# MP1584_rule.net
KiCad netlist of a schematic drawn in Altium Designer
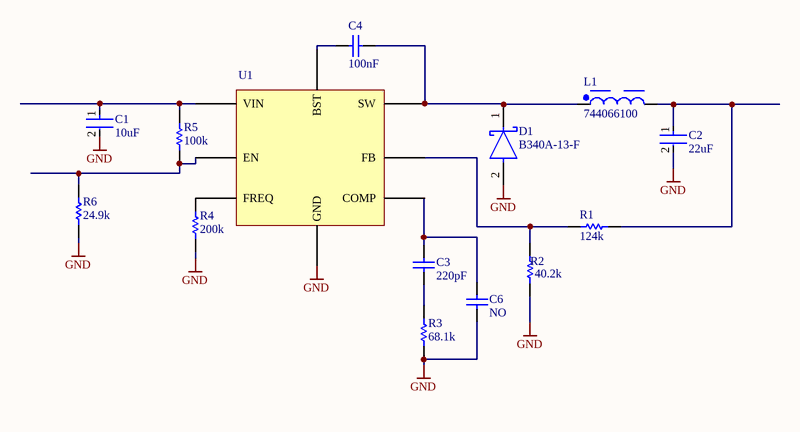
[diagram p0: MP1584_rule.SchDoc]

(export (version "E")
  (design (tool "Eeschema 10.0.6"))
  (components
    (comp (ref "C1")
      (value "10uF")
      (footprint "FP-C5750-230-0_4-MFG")
      (description "Multilayer Ceramic Capacitors 10uF ±10% 50V X5R SMD 2220")
      (fields (field (name "TOLERANCE") "10%") (field (name "VOLTAGE") "50V"))
      (libsource (lib "Altium Content Vault") (part "02cd4be3c70576c341d710602a673aa"))
    )
    (comp (ref "C2")
      (value "22uF")
      (footprint "FP-C5750-230-0_4-MFG")
      (description "Multilayer Ceramic Capacitors 10uF ±10% 50V X5R SMD 2220")
      (fields (field (name "TOLERANCE") "10%") (field (name "VOLTAGE") "50V"))
      (libsource (lib "Altium Content Vault") (part "02cd4be3c70576c341d710602a673aa"))
    )
    (comp (ref "C3")
      (value "220pF")
      (footprint "CAPC2013X88X50LL20T25")
      (fields (field (name "PART NUMBER") "C0805X221J1GACTU") (field (name "MANUFACTURER") "Kemet"))
      (libsource (lib "Altium Content Vault") (part "CAP"))
    )
    (comp (ref "C4")
      (value "100nF")
      (footprint "CAPC2013X145X48NL20T23")
      (fields (field (name "MANUFACTURER") "Vitramon") (field (name "PART NUMBER") "VJ0805Y104KXXAT"))
      (libsource (lib "Altium Content Vault") (part "CAP"))
    )
    (comp (ref "C6")
      (value "NO")
      (footprint "CAPC2013X88X50LL20T25")
      (fields (field (name "PART NUMBER") "C0805X221J1GACTU") (field (name "MANUFACTURER") "Kemet"))
      (libsource (lib "Altium Content Vault") (part "CAP"))
    )
    (comp (ref "D1")
      (value "B340A-13-F")
      (footprint "FP-SMA-MFG")
      (description "DIODE SCHOTTKY 40V 3A SMA")
      (fields (field (name "VOLTAGE") "40V"))
      (libsource (lib "Altium Content Vault") (part "1d6ec82d83fb6aee721767c19dac4b9"))
    )
    (comp (ref "L1")
      (value "744066100")
      (footprint "WE-TPC_1038")
      (fields (field (name "TOLERANCE") "30%"))
      (libsource (lib "Altium Content Vault") (part "Inductor - 2"))
    )
    (comp (ref "R1")
      (value "124k")
      (footprint "RESC2013X70X40LL20T20")
      (fields (field (name "MANUFACTURER") "Panasonic") (field (name "PART NUMBER") "ERJ-6GEYJ121V"))
      (libsource (lib "Altium Content Vault") (part "RES"))
    )
    (comp (ref "R2")
      (value "40.2k")
      (footprint "RESC2013X70X40ML20T20")
      (fields (field (name "MANUFACTURER") "Panasonic") (field (name "PART NUMBER") "ERJ6ENF4702V"))
      (libsource (lib "Altium Content Vault") (part "RES"))
    )
    (comp (ref "R3")
      (value "68.1k")
      (footprint "RESC2013X55X40ML15T20")
      (fields (field (name "MANUFACTURER") "Vishay Dale") (field (name "PART NUMBER") "TNPW080520K0BEEA"))
      (libsource (lib "Altium Content Vault") (part "RES"))
    )
    (comp (ref "R4")
      (value "200k")
      (footprint "RESC0805(2012)_L")
      (description "200K 0.125W 5% 0805 (2012 Metric)  SMD")
      (fields (field (name "TOLERANCE") "5 %") (field (name "POWER") "0.125 W"))
      (libsource (lib "Altium Content Vault") (part "RES"))
    )
    (comp (ref "R5")
      (value "100k")
      (footprint "RESC2013X50X30ML20T20")
      (fields (field (name "MANUFACTURER") "Vishay Dale") (field (name "PART NUMBER") "CRCW0805100KJNEA"))
      (libsource (lib "Altium Content Vault") (part "RES"))
    )
    (comp (ref "R6")
      (value "24.9k")
      (footprint "RESC2013X70X40LL20T20")
      (fields (field (name "PART NUMBER") "ERJ-6ENF2492V") (field (name "MANUFACTURER") "Panasonic"))
      (libsource (lib "Altium Content Vault") (part "RES"))
    )
    (comp (ref "U1")
      (value "Component_1")
      (footprint "PCBComponent_1")
      (libsource (lib "MP1584_rule") (part "MP1584"))
    )
  )
  (nets
    (net (code "1") (name "GND") (class "Default")
      (node (ref "C1") (pin "2") (pinfunction "2_2") (pintype "passive"))
      (node (ref "C2") (pin "2") (pinfunction "2_2") (pintype "passive"))
      (node (ref "C6") (pin "1") (pinfunction "1_1") (pintype "passive"))
      (node (ref "D1") (pin "2") (pinfunction "A_2") (pintype "passive"))
      (node (ref "R2") (pin "1") (pinfunction "1_1") (pintype "passive"))
      (node (ref "R3") (pin "1") (pinfunction "1_1") (pintype "passive"))
      (node (ref "R4") (pin "1") (pinfunction "1_1") (pintype "passive"))
      (node (ref "R6") (pin "1") (pinfunction "1_1") (pintype "passive"))
      (node (ref "U1") (pin "5") (pinfunction "GND_5") (pintype "passive"))
    )
    (net (code "2") (name "Net-(C2-Pad1)") (class "Default")
      (node (ref "C2") (pin "1") (pinfunction "1_1") (pintype "passive"))
      (node (ref "L1") (pin "2") (pinfunction "2_2") (pintype "passive"))
      (node (ref "R1") (pin "2") (pinfunction "2_2") (pintype "passive"))
    )
    (net (code "3") (name "Net-(C3-Pad1)") (class "Default")
      (node (ref "C3") (pin "1") (pinfunction "1_1") (pintype "passive"))
      (node (ref "R3") (pin "2") (pinfunction "2_2") (pintype "passive"))
    )
    (net (code "4") (name "Net-(D1-C)") (class "Default")
      (node (ref "C4") (pin "2") (pinfunction "2_2") (pintype "passive"))
      (node (ref "D1") (pin "1") (pinfunction "C_1") (pintype "passive"))
      (node (ref "L1") (pin "1") (pinfunction "1_1") (pintype "passive"))
      (node (ref "U1") (pin "1") (pinfunction "SW_1") (pintype "passive"))
    )
    (net (code "5") (name "Net-(U1-BST)") (class "Default")
      (node (ref "C4") (pin "1") (pinfunction "1_1") (pintype "passive"))
      (node (ref "U1") (pin "8") (pinfunction "BST_8") (pintype "passive"))
    )
    (net (code "6") (name "Net-(U1-COMP)") (class "Default")
      (node (ref "C3") (pin "2") (pinfunction "2_2") (pintype "passive"))
      (node (ref "C6") (pin "2") (pinfunction "2_2") (pintype "passive"))
      (node (ref "U1") (pin "3") (pinfunction "COMP_3") (pintype "passive"))
    )
    (net (code "7") (name "Net-(U1-EN)") (class "Default")
      (node (ref "R5") (pin "1") (pinfunction "1_1") (pintype "passive"))
      (node (ref "R6") (pin "2") (pinfunction "2_2") (pintype "passive"))
      (node (ref "U1") (pin "2") (pinfunction "EN_2") (pintype "passive"))
    )
    (net (code "8") (name "Net-(U1-FB)") (class "Default")
      (node (ref "R1") (pin "1") (pinfunction "1_1") (pintype "passive"))
      (node (ref "R2") (pin "2") (pinfunction "2_2") (pintype "passive"))
      (node (ref "U1") (pin "4") (pinfunction "FB_4") (pintype "passive"))
    )
    (net (code "9") (name "Net-(U1-FREQ)") (class "Default")
      (node (ref "R4") (pin "2") (pinfunction "2_2") (pintype "passive"))
      (node (ref "U1") (pin "6") (pinfunction "FREQ_6") (pintype "passive"))
    )
    (net (code "10") (name "Net-(U1-VIN)") (class "Default")
      (node (ref "C1") (pin "1") (pinfunction "1_1") (pintype "passive"))
      (node (ref "R5") (pin "2") (pinfunction "2_2") (pintype "passive"))
      (node (ref "U1") (pin "7") (pinfunction "VIN_7") (pintype "passive"))
    )
  )
)
